# pitching_v2.net
KiCad netlist of a schematic drawn in EAGLE
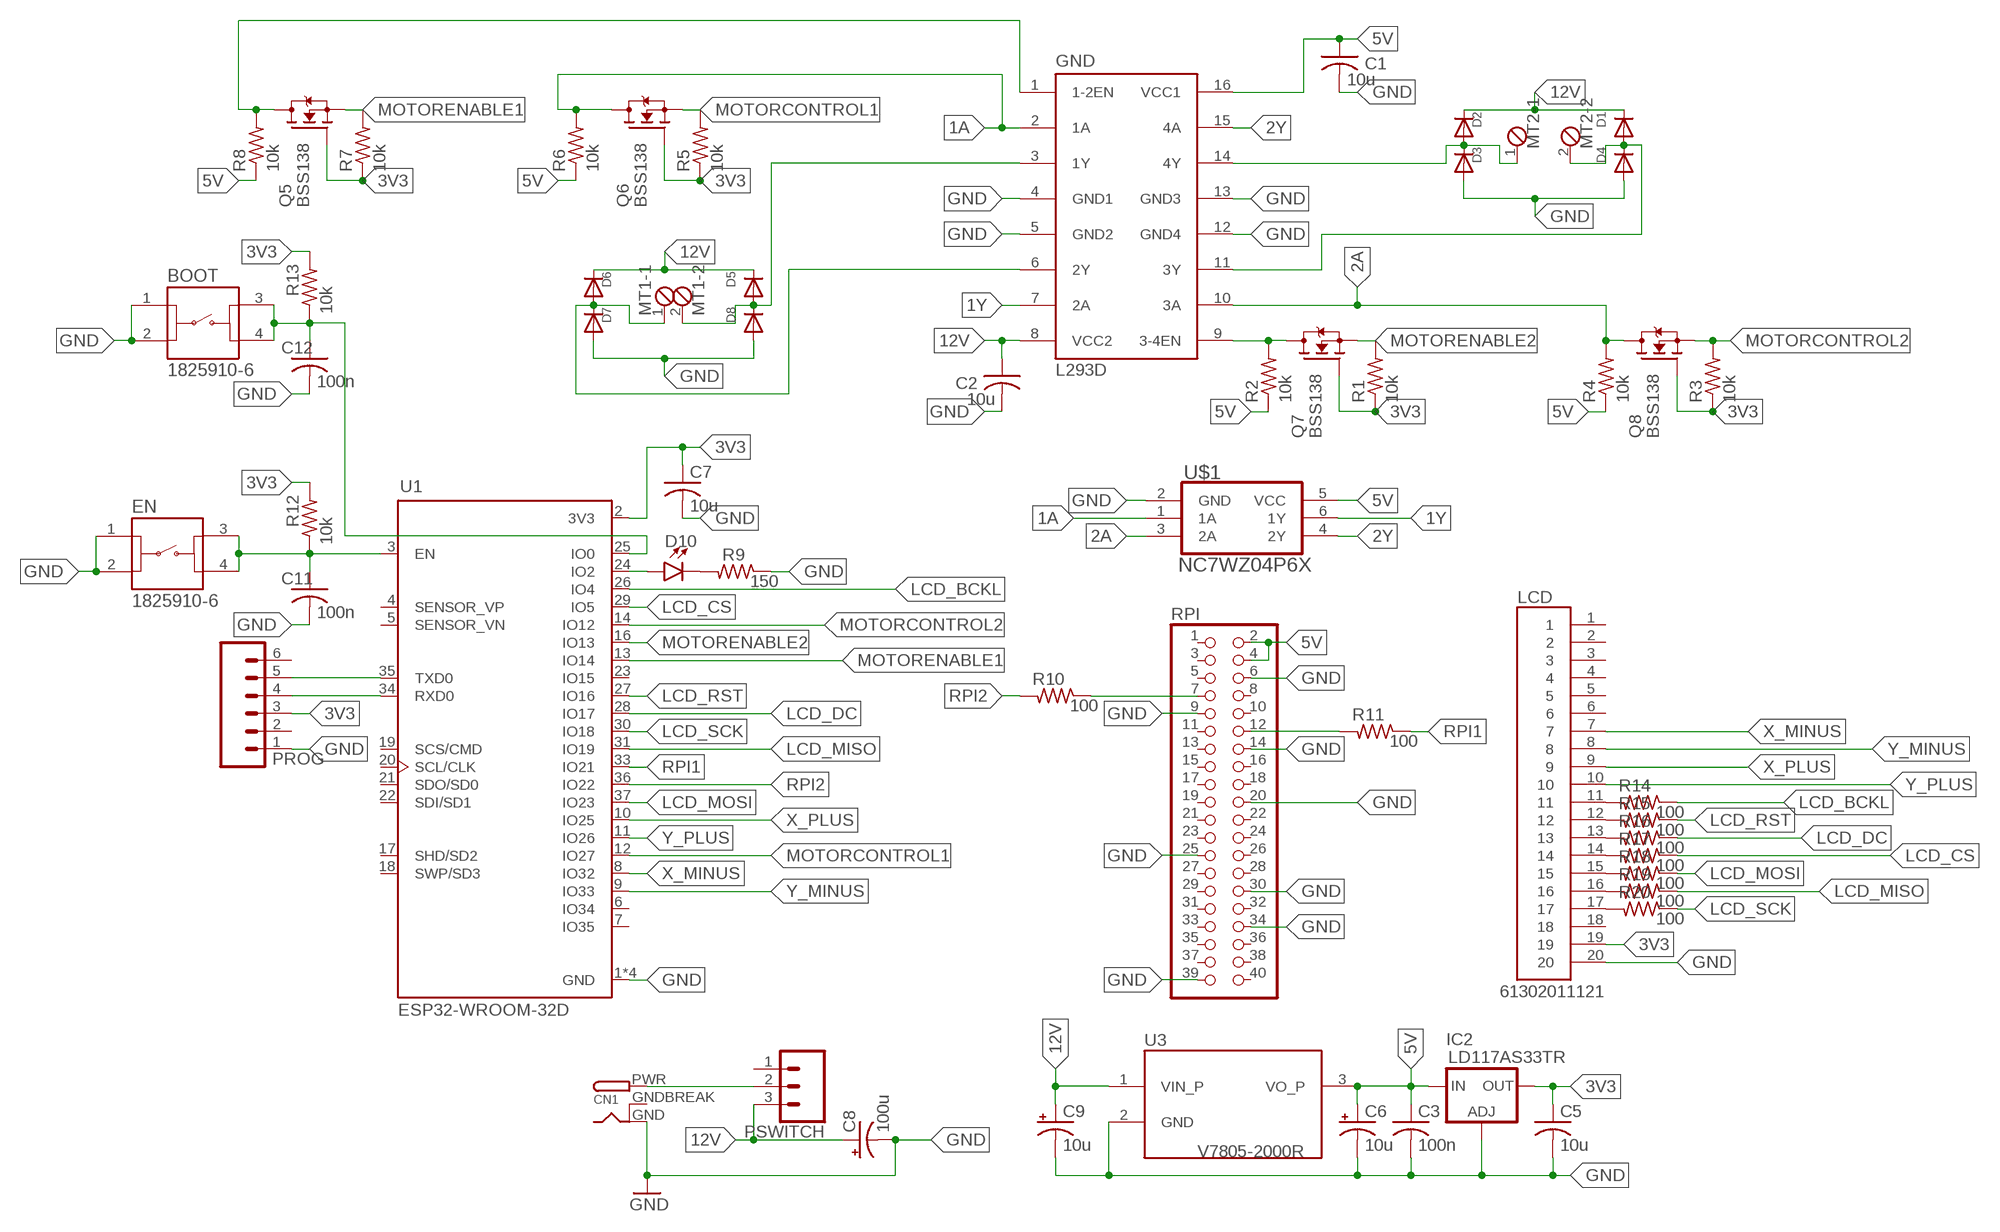
[diagram p0: schematic, sheet 1]

(export (version "E")
  (design (tool "Eeschema 10.0.6"))
  (components
    (comp (ref "BOOT")
      (value "1825910-6")
      (footprint "eagle-import:1825910-6")
      (fields
        (field (name "DIGIKEY_PART_NUMBER") "450-1650-ND")
        (field (name "MANUFACTURER") "TE Connectivity ALCOSWITCH Switches")
        (field (name "CREATED_BY") " PCBLayout.com")
      )
      (libsource (lib "eagle-import") (part "1825910-6"))
    )
    (comp (ref "C1")
      (value "10u")
      (footprint "eagle-import:C0805")
      (libsource (lib "eagle-import") (part "C-USC0805"))
    )
    (comp (ref "C2")
      (value "10u")
      (footprint "eagle-import:C0805")
      (libsource (lib "eagle-import") (part "C-USC0805"))
    )
    (comp (ref "C3")
      (value "100n")
      (footprint "eagle-import:C0805")
      (libsource (lib "eagle-import") (part "C-USC0805"))
    )
    (comp (ref "C5")
      (value "10u")
      (footprint "eagle-import:C0805")
      (libsource (lib "eagle-import") (part "C-USC0805"))
    )
    (comp (ref "C6")
      (value "10u")
      (footprint "eagle-import:153CLV-0405")
      (libsource (lib "eagle-import") (part "CPOL-US153CLV-0405"))
    )
    (comp (ref "C7")
      (value "10u")
      (footprint "eagle-import:C0805")
      (libsource (lib "eagle-import") (part "C-USC0805"))
    )
    (comp (ref "C8")
      (value "100u")
      (footprint "eagle-import:153CLV-0810")
      (libsource (lib "eagle-import") (part "CPOL-US153CLV-0810"))
    )
    (comp (ref "C9")
      (value "10u")
      (footprint "eagle-import:153CLV-0405")
      (libsource (lib "eagle-import") (part "CPOL-US153CLV-0405"))
    )
    (comp (ref "C11")
      (value "100n")
      (footprint "eagle-import:C0805")
      (libsource (lib "eagle-import") (part "C-USC0805"))
    )
    (comp (ref "C12")
      (value "100n")
      (footprint "eagle-import:C0805")
      (libsource (lib "eagle-import") (part "C-USC0805"))
    )
    (comp (ref "CN1")
      (value "DCBARRELPTH")
      (footprint "eagle-import:DCJACK_2MM_PTH")
      (libsource (lib "eagle-import") (part "DCBARRELPTH"))
    )
    (comp (ref "D1")
      (value "DIODESMA")
      (footprint "eagle-import:SMADIODE")
      (libsource (lib "eagle-import") (part "DIODESMA"))
    )
    (comp (ref "D2")
      (value "DIODESMA")
      (footprint "eagle-import:SMADIODE")
      (libsource (lib "eagle-import") (part "DIODESMA"))
    )
    (comp (ref "D3")
      (value "DIODESMA")
      (footprint "eagle-import:SMADIODE")
      (libsource (lib "eagle-import") (part "DIODESMA"))
    )
    (comp (ref "D4")
      (value "DIODESMA")
      (footprint "eagle-import:SMADIODE")
      (libsource (lib "eagle-import") (part "DIODESMA"))
    )
    (comp (ref "D5")
      (value "DIODESMA")
      (footprint "eagle-import:SMADIODE")
      (libsource (lib "eagle-import") (part "DIODESMA"))
    )
    (comp (ref "D6")
      (value "DIODESMA")
      (footprint "eagle-import:SMADIODE")
      (libsource (lib "eagle-import") (part "DIODESMA"))
    )
    (comp (ref "D7")
      (value "DIODESMA")
      (footprint "eagle-import:SMADIODE")
      (libsource (lib "eagle-import") (part "DIODESMA"))
    )
    (comp (ref "D8")
      (value "DIODESMA")
      (footprint "eagle-import:SMADIODE")
      (libsource (lib "eagle-import") (part "DIODESMA"))
    )
    (comp (ref "D10")
      (value "LED3MM")
      (footprint "eagle-import:LED_3MM")
      (libsource (lib "eagle-import") (part "LED3MM"))
    )
    (comp (ref "EN")
      (value "1825910-6")
      (footprint "eagle-import:1825910-6")
      (fields
        (field (name "DIGIKEY_PART_NUMBER") "450-1650-ND")
        (field (name "MANUFACTURER") "TE Connectivity ALCOSWITCH Switches")
        (field (name "CREATED_BY") " PCBLayout.com")
      )
      (libsource (lib "eagle-import") (part "1825910-6"))
    )
    (comp (ref "GND")
      (value "L293D")
      (footprint "eagle-import:DIL16")
      (libsource (lib "eagle-import") (part "L293D"))
    )
    (comp (ref "IC2")
      (value "LD117AS33TR")
      (footprint "eagle-import:SOT223")
      (libsource (lib "eagle-import") (part "LD117A?S33TR"))
    )
    (comp (ref "LCD")
      (value "61302011121")
      (footprint "eagle-import:61302011121")
      (fields
        (field (name "DIGIKEY_PART_NUMBER") "732-5329-ND")
        (field (name "MANUFACTURER") "Wurth Electronics Inc.")
        (field (name "CREATED_BY") "PCBLayout.com")
      )
      (libsource (lib "eagle-import") (part "61302011121"))
    )
    (comp (ref "MT1")
      (value "MPT2")
      (footprint "eagle-import:2POL254")
      (libsource (lib "eagle-import") (part "MPT2"))
    )
    (comp (ref "MT2")
      (value "MPT2")
      (footprint "eagle-import:2POL254")
      (libsource (lib "eagle-import") (part "MPT2"))
    )
    (comp (ref "PROG")
      (value "CONN_06SILK_FEMALE_PTH")
      (footprint "eagle-import:1X06")
      (libsource (lib "eagle-import") (part "CONN_06SILK_FEMALE_PTH"))
    )
    (comp (ref "PSWITCH")
      (value "CONN_03")
      (footprint "eagle-import:1X03")
      (libsource (lib "eagle-import") (part "CONN_03"))
    )
    (comp (ref "Q5")
      (value "BSS138")
      (footprint "eagle-import:SOT23")
      (fields (field (name "MF") "Fairchild"))
      (libsource (lib "eagle-import") (part "BSS138"))
    )
    (comp (ref "Q6")
      (value "BSS138")
      (footprint "eagle-import:SOT23")
      (fields (field (name "MF") "Fairchild"))
      (libsource (lib "eagle-import") (part "BSS138"))
    )
    (comp (ref "Q7")
      (value "BSS138")
      (footprint "eagle-import:SOT23")
      (fields (field (name "MF") "Fairchild"))
      (libsource (lib "eagle-import") (part "BSS138"))
    )
    (comp (ref "Q8")
      (value "BSS138")
      (footprint "eagle-import:SOT23")
      (fields (field (name "MF") "Fairchild"))
      (libsource (lib "eagle-import") (part "BSS138"))
    )
    (comp (ref "R1")
      (value "10k")
      (footprint "eagle-import:R0805")
      (libsource (lib "eagle-import") (part "R-US_R0805"))
    )
    (comp (ref "R2")
      (value "10k")
      (footprint "eagle-import:R0805")
      (libsource (lib "eagle-import") (part "R-US_R0805"))
    )
    (comp (ref "R3")
      (value "10k")
      (footprint "eagle-import:R0805")
      (libsource (lib "eagle-import") (part "R-US_R0805"))
    )
    (comp (ref "R4")
      (value "10k")
      (footprint "eagle-import:R0805")
      (libsource (lib "eagle-import") (part "R-US_R0805"))
    )
    (comp (ref "R5")
      (value "10k")
      (footprint "eagle-import:R0805")
      (libsource (lib "eagle-import") (part "R-US_R0805"))
    )
    (comp (ref "R6")
      (value "10k")
      (footprint "eagle-import:R0805")
      (libsource (lib "eagle-import") (part "R-US_R0805"))
    )
    (comp (ref "R7")
      (value "10k")
      (footprint "eagle-import:R0805")
      (libsource (lib "eagle-import") (part "R-US_R0805"))
    )
    (comp (ref "R8")
      (value "10k")
      (footprint "eagle-import:R0805")
      (libsource (lib "eagle-import") (part "R-US_R0805"))
    )
    (comp (ref "R9")
      (value "150")
      (footprint "eagle-import:R0805")
      (libsource (lib "eagle-import") (part "R-US_R0805"))
    )
    (comp (ref "R10")
      (value "100")
      (footprint "eagle-import:R0805")
      (libsource (lib "eagle-import") (part "R-US_R0805"))
    )
    (comp (ref "R11")
      (value "100")
      (footprint "eagle-import:R0805")
      (libsource (lib "eagle-import") (part "R-US_R0805"))
    )
    (comp (ref "R12")
      (value "10k")
      (footprint "eagle-import:R0805")
      (libsource (lib "eagle-import") (part "R-US_R0805"))
    )
    (comp (ref "R13")
      (value "10k")
      (footprint "eagle-import:R0805")
      (libsource (lib "eagle-import") (part "R-US_R0805"))
    )
    (comp (ref "R14")
      (value "100")
      (footprint "eagle-import:R0805")
      (libsource (lib "eagle-import") (part "R-US_R0805"))
    )
    (comp (ref "R15")
      (value "100")
      (footprint "eagle-import:R0805")
      (libsource (lib "eagle-import") (part "R-US_R0805"))
    )
    (comp (ref "R16")
      (value "100")
      (footprint "eagle-import:R0805")
      (libsource (lib "eagle-import") (part "R-US_R0805"))
    )
    (comp (ref "R17")
      (value "100")
      (footprint "eagle-import:R0805")
      (libsource (lib "eagle-import") (part "R-US_R0805"))
    )
    (comp (ref "R18")
      (value "100")
      (footprint "eagle-import:R0805")
      (libsource (lib "eagle-import") (part "R-US_R0805"))
    )
    (comp (ref "R19")
      (value "100")
      (footprint "eagle-import:R0805")
      (libsource (lib "eagle-import") (part "R-US_R0805"))
    )
    (comp (ref "R20")
      (value "100")
      (footprint "eagle-import:R0805")
      (libsource (lib "eagle-import") (part "R-US_R0805"))
    )
    (comp (ref "RPI")
      (value "PINHD-2X20")
      (footprint "eagle-import:2X20")
      (libsource (lib "eagle-import") (part "PINHD-2X20"))
    )
    (comp (ref "U$1")
      (value "NC7WZ04P6X")
      (footprint "eagle-import:SOT65P210X110-6N")
      (libsource (lib "eagle-import") (part "NC7WZ04P6X"))
    )
    (comp (ref "U1")
      (value "ESP32-WROOM-32D")
      (footprint "eagle-import:MODULE_ESP32-WROOM-32D")
      (fields (field (name "MF") "Espressif Systems"))
      (libsource (lib "eagle-import") (part "ESP32-WROOM-32D"))
    )
    (comp (ref "U3")
      (value "V7805-2000R")
      (footprint "eagle-import:CONV_V7805-2000R")
      (fields (field (name "MANUFACTURER") "CUI INC"))
      (libsource (lib "eagle-import") (part "V7805-2000R"))
    )
  )
  (nets
    (net (code "1") (name "/GNDBREAK") (class "Default")
      (node (ref "CN1") (pin "GNDBREAK") (pinfunction "GNDBREAK_GNDBREAK") (pintype "power_in"))
    )
    (net (code "2") (name "1A") (class "Default")
      (node (ref "GND") (pin "2") (pinfunction "1A_2") (pintype "input"))
      (node (ref "Q6") (pin "3") (pinfunction "D_3") (pintype "passive"))
      (node (ref "R6") (pin "2") (pinfunction "2_2") (pintype "passive"))
      (node (ref "U$1") (pin "1") (pinfunction "1A_1") (pintype "passive"))
    )
    (net (code "3") (name "1Y") (class "Default")
      (node (ref "GND") (pin "7") (pinfunction "2A_7") (pintype "input"))
      (node (ref "U$1") (pin "6") (pinfunction "1Y_6") (pintype "passive"))
    )
    (net (code "4") (name "2A") (class "Default")
      (node (ref "GND") (pin "10") (pinfunction "3A_10") (pintype "input"))
      (node (ref "Q8") (pin "3") (pinfunction "D_3") (pintype "passive"))
      (node (ref "R4") (pin "2") (pinfunction "2_2") (pintype "passive"))
      (node (ref "U$1") (pin "3") (pinfunction "2A_3") (pintype "passive"))
    )
    (net (code "5") (name "2Y") (class "Default")
      (node (ref "GND") (pin "15") (pinfunction "4A_15") (pintype "input"))
      (node (ref "U$1") (pin "4") (pinfunction "2Y_4") (pintype "passive"))
    )
    (net (code "6") (name "3V3") (class "Default")
      (node (ref "C5") (pin "1") (pinfunction "1_1") (pintype "passive"))
      (node (ref "C7") (pin "1") (pinfunction "1_1") (pintype "passive"))
      (node (ref "IC2") (pin "4") (pinfunction "OUT_4") (pintype "passive"))
      (node (ref "LCD") (pin "19") (pinfunction "19_19") (pintype "passive"))
      (node (ref "PROG") (pin "3") (pinfunction "3_3") (pintype "passive"))
      (node (ref "Q5") (pin "1") (pinfunction "G_1") (pintype "passive"))
      (node (ref "Q6") (pin "1") (pinfunction "G_1") (pintype "passive"))
      (node (ref "Q7") (pin "1") (pinfunction "G_1") (pintype "passive"))
      (node (ref "Q8") (pin "1") (pinfunction "G_1") (pintype "passive"))
      (node (ref "R1") (pin "1") (pinfunction "1_1") (pintype "passive"))
      (node (ref "R12") (pin "2") (pinfunction "2_2") (pintype "passive"))
      (node (ref "R13") (pin "2") (pinfunction "2_2") (pintype "passive"))
      (node (ref "R3") (pin "1") (pinfunction "1_1") (pintype "passive"))
      (node (ref "R5") (pin "1") (pinfunction "1_1") (pintype "passive"))
      (node (ref "R7") (pin "1") (pinfunction "1_1") (pintype "passive"))
      (node (ref "U1") (pin "2") (pinfunction "3V3_2") (pintype "power_in"))
    )
    (net (code "7") (name "5V") (class "Default")
      (node (ref "C1") (pin "1") (pinfunction "1_1") (pintype "passive"))
      (node (ref "C3") (pin "1") (pinfunction "1_1") (pintype "passive"))
      (node (ref "C6") (pin "+") (pinfunction "+_+") (pintype "passive"))
      (node (ref "GND") (pin "16") (pinfunction "VCC1_16") (pintype "power_in"))
      (node (ref "IC2") (pin "3") (pinfunction "IN_3") (pintype "input"))
      (node (ref "R2") (pin "1") (pinfunction "1_1") (pintype "passive"))
      (node (ref "R4") (pin "1") (pinfunction "1_1") (pintype "passive"))
      (node (ref "R6") (pin "1") (pinfunction "1_1") (pintype "passive"))
      (node (ref "R8") (pin "1") (pinfunction "1_1") (pintype "passive"))
      (node (ref "RPI") (pin "2") (pinfunction "2_2") (pintype "passive"))
      (node (ref "RPI") (pin "4") (pinfunction "4_4") (pintype "passive"))
      (node (ref "U$1") (pin "5") (pinfunction "VCC_5") (pintype "passive"))
      (node (ref "U3") (pin "3") (pinfunction "VO_P_3") (pintype "output"))
    )
    (net (code "8") (name "12V") (class "Default")
      (node (ref "C2") (pin "1") (pinfunction "1_1") (pintype "passive"))
      (node (ref "C8") (pin "+") (pinfunction "+_+") (pintype "passive"))
      (node (ref "C9") (pin "+") (pinfunction "+_+") (pintype "passive"))
      (node (ref "D1") (pin "C") (pinfunction "C_C") (pintype "passive"))
      (node (ref "D2") (pin "C") (pinfunction "C_C") (pintype "passive"))
      (node (ref "D5") (pin "C") (pinfunction "C_C") (pintype "passive"))
      (node (ref "D6") (pin "C") (pinfunction "C_C") (pintype "passive"))
      (node (ref "GND") (pin "8") (pinfunction "VCC2_8") (pintype "power_in"))
      (node (ref "PSWITCH") (pin "3") (pinfunction "3_3") (pintype "passive"))
      (node (ref "U3") (pin "1") (pinfunction "VIN_P_1") (pintype "input"))
    )
    (net (code "9") (name "GND") (class "Default")
      (node (ref "BOOT") (pin "1") (pinfunction "1_1") (pintype "passive"))
      (node (ref "BOOT") (pin "2") (pinfunction "2_2") (pintype "passive"))
      (node (ref "C1") (pin "2") (pinfunction "2_2") (pintype "passive"))
      (node (ref "C11") (pin "2") (pinfunction "2_2") (pintype "passive"))
      (node (ref "C12") (pin "2") (pinfunction "2_2") (pintype "passive"))
      (node (ref "C2") (pin "2") (pinfunction "2_2") (pintype "passive"))
      (node (ref "C3") (pin "2") (pinfunction "2_2") (pintype "passive"))
      (node (ref "C5") (pin "2") (pinfunction "2_2") (pintype "passive"))
      (node (ref "C6") (pin "-") (pinfunction "-_-") (pintype "passive"))
      (node (ref "C7") (pin "2") (pinfunction "2_2") (pintype "passive"))
      (node (ref "C8") (pin "-") (pinfunction "-_-") (pintype "passive"))
      (node (ref "C9") (pin "-") (pinfunction "-_-") (pintype "passive"))
      (node (ref "CN1") (pin "GND") (pinfunction "GND_GND") (pintype "power_in"))
      (node (ref "D3") (pin "A") (pinfunction "A_A") (pintype "passive"))
      (node (ref "D4") (pin "A") (pinfunction "A_A") (pintype "passive"))
      (node (ref "D7") (pin "A") (pinfunction "A_A") (pintype "passive"))
      (node (ref "D8") (pin "A") (pinfunction "A_A") (pintype "passive"))
      (node (ref "EN") (pin "1") (pinfunction "1_1") (pintype "passive"))
      (node (ref "EN") (pin "2") (pinfunction "2_2") (pintype "passive"))
      (node (ref "GND") (pin "12") (pinfunction "GND4_12") (pintype "power_in"))
      (node (ref "GND") (pin "13") (pinfunction "GND3_13") (pintype "power_in"))
      (node (ref "GND") (pin "4") (pinfunction "GND1_4") (pintype "power_in"))
      (node (ref "GND") (pin "5") (pinfunction "GND2_5") (pintype "power_in"))
      (node (ref "IC2") (pin "1") (pinfunction "ADJ_1") (pintype "input"))
      (node (ref "LCD") (pin "20") (pinfunction "20_20") (pintype "passive"))
      (node (ref "PROG") (pin "1") (pinfunction "1_1") (pintype "passive"))
      (node (ref "R9") (pin "1") (pinfunction "1_1") (pintype "passive"))
      (node (ref "RPI") (pin "14") (pinfunction "14_14") (pintype "passive"))
      (node (ref "RPI") (pin "20") (pinfunction "20_20") (pintype "passive"))
      (node (ref "RPI") (pin "25") (pinfunction "25_25") (pintype "passive"))
      (node (ref "RPI") (pin "30") (pinfunction "30_30") (pintype "passive"))
      (node (ref "RPI") (pin "34") (pinfunction "34_34") (pintype "passive"))
      (node (ref "RPI") (pin "39") (pinfunction "39_39") (pintype "passive"))
      (node (ref "RPI") (pin "6") (pinfunction "6_6") (pintype "passive"))
      (node (ref "RPI") (pin "9") (pinfunction "9_9") (pintype "passive"))
      (node (ref "U$1") (pin "2") (pinfunction "GND_2") (pintype "passive"))
      (node (ref "U1") (pin "1") (pinfunction "GND_1") (pintype "power_in"))
      (node (ref "U1") (pin "15") (pinfunction "GND_15") (pintype "power_in"))
      (node (ref "U1") (pin "38") (pinfunction "GND_38") (pintype "power_in"))
      (node (ref "U1") (pin "39") (pinfunction "GND_39") (pintype "power_in"))
      (node (ref "U3") (pin "2") (pinfunction "GND_2") (pintype "power_in"))
    )
    (net (code "10") (name "LCD_BCKL") (class "Default")
      (node (ref "R14") (pin "1") (pinfunction "1_1") (pintype "passive"))
      (node (ref "U1") (pin "26") (pinfunction "IO4_26") (pintype "bidirectional"))
    )
    (net (code "11") (name "LCD_CS") (class "Default")
      (node (ref "R17") (pin "1") (pinfunction "1_1") (pintype "passive"))
      (node (ref "U1") (pin "29") (pinfunction "IO5_29") (pintype "bidirectional"))
    )
    (net (code "12") (name "LCD_DC") (class "Default")
      (node (ref "R16") (pin "1") (pinfunction "1_1") (pintype "passive"))
      (node (ref "U1") (pin "28") (pinfunction "IO17_28") (pintype "bidirectional"))
    )
    (net (code "13") (name "LCD_MISO") (class "Default")
      (node (ref "R19") (pin "1") (pinfunction "1_1") (pintype "passive"))
      (node (ref "U1") (pin "31") (pinfunction "IO19_31") (pintype "bidirectional"))
    )
    (net (code "14") (name "LCD_MOSI") (class "Default")
      (node (ref "R18") (pin "1") (pinfunction "1_1") (pintype "passive"))
      (node (ref "U1") (pin "37") (pinfunction "IO23_37") (pintype "bidirectional"))
    )
    (net (code "15") (name "LCD_RST") (class "Default")
      (node (ref "R15") (pin "1") (pinfunction "1_1") (pintype "passive"))
      (node (ref "U1") (pin "27") (pinfunction "IO16_27") (pintype "bidirectional"))
    )
    (net (code "16") (name "LCD_SCK") (class "Default")
      (node (ref "R20") (pin "1") (pinfunction "1_1") (pintype "passive"))
      (node (ref "U1") (pin "30") (pinfunction "IO18_30") (pintype "bidirectional"))
    )
    (net (code "17") (name "MOTORCONTROL1") (class "Default")
      (node (ref "Q6") (pin "2") (pinfunction "S_2") (pintype "passive"))
      (node (ref "R5") (pin "2") (pinfunction "2_2") (pintype "passive"))
      (node (ref "U1") (pin "12") (pinfunction "IO27_12") (pintype "bidirectional"))
    )
    (net (code "18") (name "MOTORCONTROL2") (class "Default")
      (node (ref "Q8") (pin "2") (pinfunction "S_2") (pintype "passive"))
      (node (ref "R3") (pin "2") (pinfunction "2_2") (pintype "passive"))
      (node (ref "U1") (pin "14") (pinfunction "IO12_14") (pintype "bidirectional"))
    )
    (net (code "19") (name "MOTORENABLE1") (class "Default")
      (node (ref "Q5") (pin "2") (pinfunction "S_2") (pintype "passive"))
      (node (ref "R7") (pin "2") (pinfunction "2_2") (pintype "passive"))
      (node (ref "U1") (pin "13") (pinfunction "IO14_13") (pintype "bidirectional"))
    )
    (net (code "20") (name "MOTORENABLE2") (class "Default")
      (node (ref "Q7") (pin "2") (pinfunction "S_2") (pintype "passive"))
      (node (ref "R1") (pin "2") (pinfunction "2_2") (pintype "passive"))
      (node (ref "U1") (pin "16") (pinfunction "IO13_16") (pintype "bidirectional"))
    )
    (net (code "21") (name "Net-(CN1-PadPWR)") (class "Default")
      (node (ref "CN1") (pin "PWR") (pinfunction "PWR_PWR") (pintype "power_in"))
      (node (ref "PSWITCH") (pin "2") (pinfunction "2_2") (pintype "passive"))
    )
    (net (code "22") (name "Net-(D10-C)") (class "Default")
      (node (ref "D10") (pin "K") (pinfunction "C_K") (pintype "passive"))
      (node (ref "R9") (pin "2") (pinfunction "2_2") (pintype "passive"))
    )
    (net (code "23") (name "Net-(GND-1-2EN)") (class "Default")
      (node (ref "GND") (pin "1") (pinfunction "1-2EN_1") (pintype "input"))
      (node (ref "Q5") (pin "3") (pinfunction "D_3") (pintype "passive"))
      (node (ref "R8") (pin "2") (pinfunction "2_2") (pintype "passive"))
    )
    (net (code "24") (name "Net-(GND-1Y)") (class "Default")
      (node (ref "D5") (pin "A") (pinfunction "A_A") (pintype "passive"))
      (node (ref "D8") (pin "C") (pinfunction "C_C") (pintype "passive"))
      (node (ref "GND") (pin "3") (pinfunction "1Y_3") (pintype "output"))
      (node (ref "MT1") (pin "2") (pinfunction "1_2") (pintype "passive"))
    )
    (net (code "25") (name "Net-(GND-2Y)") (class "Default")
      (node (ref "D6") (pin "A") (pinfunction "A_A") (pintype "passive"))
      (node (ref "D7") (pin "C") (pinfunction "C_C") (pintype "passive"))
      (node (ref "GND") (pin "6") (pinfunction "2Y_6") (pintype "output"))
      (node (ref "MT1") (pin "1") (pinfunction "1_1") (pintype "passive"))
    )
    (net (code "26") (name "Net-(GND-3-4EN)") (class "Default")
      (node (ref "GND") (pin "9") (pinfunction "3-4EN_9") (pintype "input"))
      (node (ref "Q7") (pin "3") (pinfunction "D_3") (pintype "passive"))
      (node (ref "R2") (pin "2") (pinfunction "2_2") (pintype "passive"))
    )
    (net (code "27") (name "Net-(GND-3Y)") (class "Default")
      (node (ref "D1") (pin "A") (pinfunction "A_A") (pintype "passive"))
      (node (ref "D4") (pin "C") (pinfunction "C_C") (pintype "passive"))
      (node (ref "GND") (pin "11") (pinfunction "3Y_11") (pintype "output"))
      (node (ref "MT2") (pin "2") (pinfunction "1_2") (pintype "passive"))
    )
    (net (code "28") (name "Net-(GND-4Y)") (class "Default")
      (node (ref "D2") (pin "A") (pinfunction "A_A") (pintype "passive"))
      (node (ref "D3") (pin "C") (pinfunction "C_C") (pintype "passive"))
      (node (ref "GND") (pin "14") (pinfunction "4Y_14") (pintype "output"))
      (node (ref "MT2") (pin "1") (pinfunction "1_1") (pintype "passive"))
    )
    (net (code "29") (name "Net-(LCD-Pad11)") (class "Default")
      (node (ref "LCD") (pin "11") (pinfunction "11_11") (pintype "passive"))
      (node (ref "R14") (pin "2") (pinfunction "2_2") (pintype "passive"))
    )
    (net (code "30") (name "Net-(LCD-Pad12)") (class "Default")
      (node (ref "LCD") (pin "12") (pinfunction "12_12") (pintype "passive"))
      (node (ref "R15") (pin "2") (pinfunction "2_2") (pintype "passive"))
    )
    (net (code "31") (name "Net-(LCD-Pad13)") (class "Default")
      (node (ref "LCD") (pin "13") (pinfunction "13_13") (pintype "passive"))
      (node (ref "R16") (pin "2") (pinfunction "2_2") (pintype "passive"))
    )
    (net (code "32") (name "Net-(LCD-Pad14)") (class "Default")
      (node (ref "LCD") (pin "14") (pinfunction "14_14") (pintype "passive"))
      (node (ref "R17") (pin "2") (pinfunction "2_2") (pintype "passive"))
    )
    (net (code "33") (name "Net-(LCD-Pad15)") (class "Default")
      (node (ref "LCD") (pin "15") (pinfunction "15_15") (pintype "passive"))
      (node (ref "R18") (pin "2") (pinfunction "2_2") (pintype "passive"))
    )
    (net (code "34") (name "Net-(LCD-Pad16)") (class "Default")
      (node (ref "LCD") (pin "16") (pinfunction "16_16") (pintype "passive"))
      (node (ref "R19") (pin "2") (pinfunction "2_2") (pintype "passive"))
    )
    (net (code "35") (name "Net-(LCD-Pad17)") (class "Default")
      (node (ref "LCD") (pin "17") (pinfunction "17_17") (pintype "passive"))
      (node (ref "R20") (pin "2") (pinfunction "2_2") (pintype "passive"))
    )
    (net (code "36") (name "Net-(R10-Pad1)") (class "Default")
      (node (ref "R10") (pin "1") (pinfunction "1_1") (pintype "passive"))
      (node (ref "RPI") (pin "7") (pinfunction "7_7") (pintype "passive"))
    )
    (net (code "37") (name "Net-(R11-Pad2)") (class "Default")
      (node (ref "R11") (pin "2") (pinfunction "2_2") (pintype "passive"))
      (node (ref "RPI") (pin "12") (pinfunction "12_12") (pintype "passive"))
    )
    (net (code "38") (name "Net-(U1-EN)") (class "Default")
      (node (ref "C11") (pin "1") (pinfunction "1_1") (pintype "passive"))
      (node (ref "EN") (pin "3") (pinfunction "3_3") (pintype "passive"))
      (node (ref "EN") (pin "4") (pinfunction "4_4") (pintype "passive"))
      (node (ref "R12") (pin "1") (pinfunction "1_1") (pintype "passive"))
      (node (ref "U1") (pin "3") (pinfunction "EN_3") (pintype "input"))
    )
    (net (code "39") (name "Net-(U1-IO0)") (class "Default")
      (node (ref "BOOT") (pin "3") (pinfunction "3_3") (pintype "passive"))
      (node (ref "BOOT") (pin "4") (pinfunction "4_4") (pintype "passive"))
      (node (ref "C12") (pin "1") (pinfunction "1_1") (pintype "passive"))
      (node (ref "R13") (pin "1") (pinfunction "1_1") (pintype "passive"))
      (node (ref "U1") (pin "25") (pinfunction "IO0_25") (pintype "bidirectional"))
    )
    (net (code "40") (name "Net-(U1-IO2)") (class "Default")
      (node (ref "D10") (pin "A") (pinfunction "A_A") (pintype "passive"))
      (node (ref "U1") (pin "24") (pinfunction "IO2_24") (pintype "bidirectional"))
    )
    (net (code "41") (name "Net-(U1-RXD0)") (class "Default")
      (node (ref "PROG") (pin "4") (pinfunction "4_4") (pintype "passive"))
      (node (ref "U1") (pin "34") (pinfunction "RXD0_34") (pintype "bidirectional"))
    )
    (net (code "42") (name "Net-(U1-TXD0)") (class "Default")
      (node (ref "PROG") (pin "5") (pinfunction "5_5") (pintype "passive"))
      (node (ref "U1") (pin "35") (pinfunction "TXD0_35") (pintype "bidirectional"))
    )
    (net (code "43") (name "RPI1") (class "Default")
      (node (ref "R11") (pin "1") (pinfunction "1_1") (pintype "passive"))
      (node (ref "U1") (pin "33") (pinfunction "IO21_33") (pintype "bidirectional"))
    )
    (net (code "44") (name "RPI2") (class "Default")
      (node (ref "R10") (pin "2") (pinfunction "2_2") (pintype "passive"))
      (node (ref "U1") (pin "36") (pinfunction "IO22_36") (pintype "bidirectional"))
    )
    (net (code "45") (name "X_MINUS") (class "Default")
      (node (ref "LCD") (pin "7") (pinfunction "7_7") (pintype "passive"))
      (node (ref "U1") (pin "8") (pinfunction "IO32_8") (pintype "bidirectional"))
    )
    (net (code "46") (name "X_PLUS") (class "Default")
      (node (ref "LCD") (pin "9") (pinfunction "9_9") (pintype "passive"))
      (node (ref "U1") (pin "10") (pinfunction "IO25_10") (pintype "bidirectional"))
    )
    (net (code "47") (name "Y_MINUS") (class "Default")
      (node (ref "LCD") (pin "8") (pinfunction "8_8") (pintype "passive"))
      (node (ref "U1") (pin "9") (pinfunction "IO33_9") (pintype "bidirectional"))
    )
    (net (code "48") (name "Y_PLUS") (class "Default")
      (node (ref "LCD") (pin "10") (pinfunction "10_10") (pintype "passive"))
      (node (ref "U1") (pin "11") (pinfunction "IO26_11") (pintype "bidirectional"))
    )
    (net (code "49") (name "unconnected-(LCD-Pad1)") (class "Default")
      (node (ref "LCD") (pin "1") (pinfunction "1_1") (pintype "passive"))
    )
    (net (code "50") (name "unconnected-(LCD-Pad2)") (class "Default")
      (node (ref "LCD") (pin "2") (pinfunction "2_2") (pintype "passive"))
    )
    (net (code "51") (name "unconnected-(LCD-Pad3)") (class "Default")
      (node (ref "LCD") (pin "3") (pinfunction "3_3") (pintype "passive"))
    )
    (net (code "52") (name "unconnected-(LCD-Pad4)") (class "Default")
      (node (ref "LCD") (pin "4") (pinfunction "4_4") (pintype "passive"))
    )
    (net (code "53") (name "unconnected-(LCD-Pad5)") (class "Default")
      (node (ref "LCD") (pin "5") (pinfunction "5_5") (pintype "passive"))
    )
    (net (code "54") (name "unconnected-(LCD-Pad6)") (class "Default")
      (node (ref "LCD") (pin "6") (pinfunction "6_6") (pintype "passive"))
    )
    (net (code "55") (name "unconnected-(LCD-Pad18)") (class "Default")
      (node (ref "LCD") (pin "18") (pinfunction "18_18") (pintype "passive"))
    )
    (net (code "56") (name "unconnected-(PROG-Pad2)") (class "Default")
      (node (ref "PROG") (pin "2") (pinfunction "2_2") (pintype "passive"))
    )
    (net (code "57") (name "unconnected-(PROG-Pad6)") (class "Default")
      (node (ref "PROG") (pin "6") (pinfunction "6_6") (pintype "passive"))
    )
    (net (code "58") (name "unconnected-(PSWITCH-Pad1)") (class "Default")
      (node (ref "PSWITCH") (pin "1") (pinfunction "1_1") (pintype "passive"))
    )
    (net (code "59") (name "unconnected-(RPI-Pad1)") (class "Default")
      (node (ref "RPI") (pin "1") (pinfunction "1_1") (pintype "passive"))
    )
    (net (code "60") (name "unconnected-(RPI-Pad3)") (class "Default")
      (node (ref "RPI") (pin "3") (pinfunction "3_3") (pintype "passive"))
    )
    (net (code "61") (name "unconnected-(RPI-Pad5)") (class "Default")
      (node (ref "RPI") (pin "5") (pinfunction "5_5") (pintype "passive"))
    )
    (net (code "62") (name "unconnected-(RPI-Pad8)") (class "Default")
      (node (ref "RPI") (pin "8") (pinfunction "8_8") (pintype "passive"))
    )
    (net (code "63") (name "unconnected-(RPI-Pad10)") (class "Default")
      (node (ref "RPI") (pin "10") (pinfunction "10_10") (pintype "passive"))
    )
    (net (code "64") (name "unconnected-(RPI-Pad11)") (class "Default")
      (node (ref "RPI") (pin "11") (pinfunction "11_11") (pintype "passive"))
    )
    (net (code "65") (name "unconnected-(RPI-Pad13)") (class "Default")
      (node (ref "RPI") (pin "13") (pinfunction "13_13") (pintype "passive"))
    )
    (net (code "66") (name "unconnected-(RPI-Pad15)") (class "Default")
      (node (ref "RPI") (pin "15") (pinfunction "15_15") (pintype "passive"))
    )
    (net (code "67") (name "unconnected-(RPI-Pad16)") (class "Default")
      (node (ref "RPI") (pin "16") (pinfunction "16_16") (pintype "passive"))
    )
    (net (code "68") (name "unconnected-(RPI-Pad17)") (class "Default")
      (node (ref "RPI") (pin "17") (pinfunction "17_17") (pintype "passive"))
    )
    (net (code "69") (name "unconnected-(RPI-Pad18)") (class "Default")
      (node (ref "RPI") (pin "18") (pinfunction "18_18") (pintype "passive"))
    )
    (net (code "70") (name "unconnected-(RPI-Pad19)") (class "Default")
      (node (ref "RPI") (pin "19") (pinfunction "19_19") (pintype "passive"))
    )
    (net (code "71") (name "unconnected-(RPI-Pad21)") (class "Default")
      (node (ref "RPI") (pin "21") (pinfunction "21_21") (pintype "passive"))
    )
    (net (code "72") (name "unconnected-(RPI-Pad22)") (class "Default")
      (node (ref "RPI") (pin "22") (pinfunction "22_22") (pintype "passive"))
    )
    (net (code "73") (name "unconnected-(RPI-Pad23)") (class "Default")
      (node (ref "RPI") (pin "23") (pinfunction "23_23") (pintype "passive"))
    )
    (net (code "74") (name "unconnected-(RPI-Pad24)") (class "Default")
      (node (ref "RPI") (pin "24") (pinfunction "24_24") (pintype "passive"))
    )
    (net (code "75") (name "unconnected-(RPI-Pad26)") (class "Default")
      (node (ref "RPI") (pin "26") (pinfunction "26_26") (pintype "passive"))
    )
    (net (code "76") (name "unconnected-(RPI-Pad27)") (class "Default")
      (node (ref "RPI") (pin "27") (pinfunction "27_27") (pintype "passive"))
    )
    (net (code "77") (name "unconnected-(RPI-Pad28)") (class "Default")
      (node (ref "RPI") (pin "28") (pinfunction "28_28") (pintype "passive"))
    )
    (net (code "78") (name "unconnected-(RPI-Pad29)") (class "Default")
      (node (ref "RPI") (pin "29") (pinfunction "29_29") (pintype "passive"))
    )
    (net (code "79") (name "unconnected-(RPI-Pad31)") (class "Default")
      (node (ref "RPI") (pin "31") (pinfunction "31_31") (pintype "passive"))
    )
    (net (code "80") (name "unconnected-(RPI-Pad32)") (class "Default")
      (node (ref "RPI") (pin "32") (pinfunction "32_32") (pintype "passive"))
    )
    (net (code "81") (name "unconnected-(RPI-Pad33)") (class "Default")
      (node (ref "RPI") (pin "33") (pinfunction "33_33") (pintype "passive"))
    )
    (net (code "82") (name "unconnected-(RPI-Pad35)") (class "Default")
      (node (ref "RPI") (pin "35") (pinfunction "35_35") (pintype "passive"))
    )
    (net (code "83") (name "unconnected-(RPI-Pad36)") (class "Default")
      (node (ref "RPI") (pin "36") (pinfunction "36_36") (pintype "passive"))
    )
    (net (code "84") (name "unconnected-(RPI-Pad37)") (class "Default")
      (node (ref "RPI") (pin "37") (pinfunction "37_37") (pintype "passive"))
    )
    (net (code "85") (name "unconnected-(RPI-Pad38)") (class "Default")
      (node (ref "RPI") (pin "38") (pinfunction "38_38") (pintype "passive"))
    )
    (net (code "86") (name "unconnected-(RPI-Pad40)") (class "Default")
      (node (ref "RPI") (pin "40") (pinfunction "40_40") (pintype "passive"))
    )
    (net (code "87") (name "unconnected-(U1-IO15-Pad23)") (class "Default")
      (node (ref "U1") (pin "23") (pinfunction "IO15_23") (pintype "bidirectional"))
    )
    (net (code "88") (name "unconnected-(U1-IO34-Pad6)") (class "Default")
      (node (ref "U1") (pin "6") (pinfunction "IO34_6") (pintype "bidirectional"))
    )
    (net (code "89") (name "unconnected-(U1-IO35-Pad7)") (class "Default")
      (node (ref "U1") (pin "7") (pinfunction "IO35_7") (pintype "bidirectional"))
    )
    (net (code "90") (name "unconnected-(U1-SCL{slash}CLK-Pad20)") (class "Default")
      (node (ref "U1") (pin "20") (pinfunction "SCL/CLK_20") (pintype "bidirectional"))
    )
    (net (code "91") (name "unconnected-(U1-SCS{slash}CMD-Pad19)") (class "Default")
      (node (ref "U1") (pin "19") (pinfunction "SCS/CMD_19") (pintype "bidirectional"))
    )
    (net (code "92") (name "unconnected-(U1-SDI{slash}SD1-Pad22)") (class "Default")
      (node (ref "U1") (pin "22") (pinfunction "SDI/SD1_22") (pintype "bidirectional"))
    )
    (net (code "93") (name "unconnected-(U1-SDO{slash}SD0-Pad21)") (class "Default")
      (node (ref "U1") (pin "21") (pinfunction "SDO/SD0_21") (pintype "bidirectional"))
    )
    (net (code "94") (name "unconnected-(U1-SENSOR_VN-Pad5)") (class "Default")
      (node (ref "U1") (pin "5") (pinfunction "SENSOR_VN_5") (pintype "input"))
    )
    (net (code "95") (name "unconnected-(U1-SENSOR_VP-Pad4)") (class "Default")
      (node (ref "U1") (pin "4") (pinfunction "SENSOR_VP_4") (pintype "input"))
    )
    (net (code "96") (name "unconnected-(U1-SHD{slash}SD2-Pad17)") (class "Default")
      (node (ref "U1") (pin "17") (pinfunction "SHD/SD2_17") (pintype "bidirectional"))
    )
    (net (code "97") (name "unconnected-(U1-SWP{slash}SD3-Pad18)") (class "Default")
      (node (ref "U1") (pin "18") (pinfunction "SWP/SD3_18") (pintype "bidirectional"))
    )
  )
)
